# OMODRI_Gate_Driver_1.net
KiCad netlist of a schematic drawn in Altium Designer
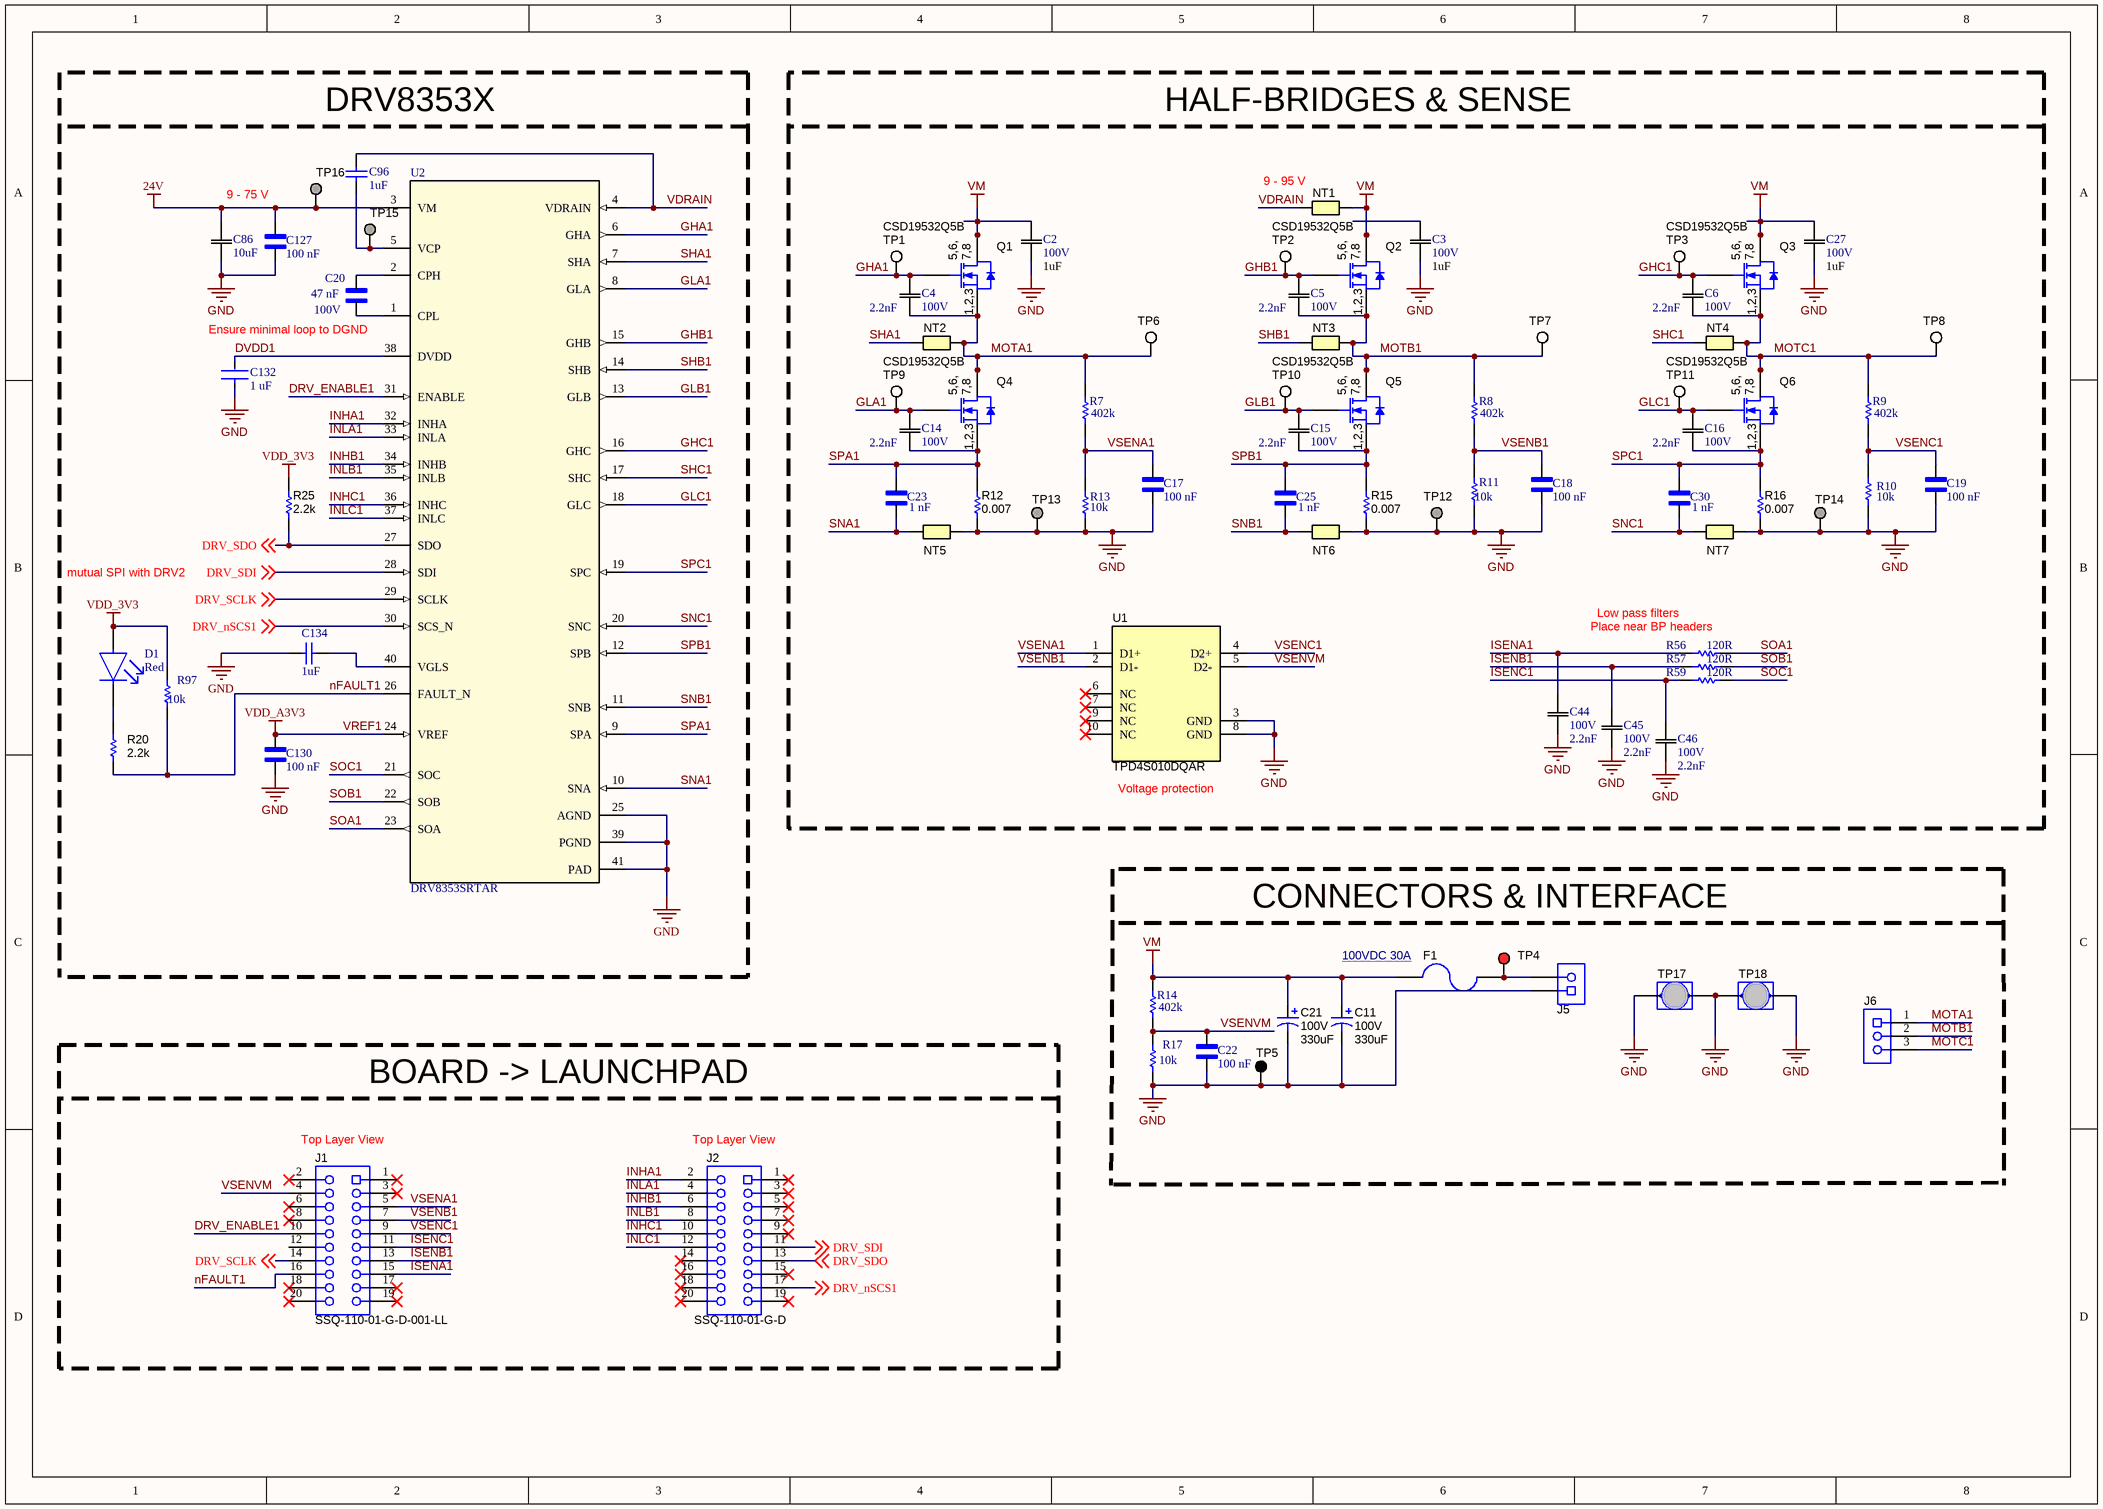
[diagram p0: OMODRI_Gate_Driver_1.SchDoc]

(export (version "E")
  (design (tool "Eeschema 10.0.6"))
  (components
    (comp (ref "C2")
      (value "1uF")
      (footprint "0805_AVX")
      (description "Cap Ceramic 1uF 100V X7R 10% Pad SMD 0805 Soft Termination 125C Automotive T/R")
      (fields
        (field (name "MANUFACTURER_PART_NUMBER") "08051C102K4Z2A")
        (field (name "MANUFACTURER") "Kyocera AVX")
        (field (name "VOLTAGE") "100V")
        (field (name "COPYRIGHT") "Copyright (C) 2018 Accelerated Designs. All rights reserved")
      )
      (libsource (lib "AVX-Capacitor") (part "08051C105K4Z2A"))
    )
    (comp (ref "C3")
      (value "1uF")
      (footprint "0805_AVX")
      (description "Cap Ceramic 1uF 100V X7R 10% Pad SMD 0805 Soft Termination 125C Automotive T/R")
      (fields
        (field (name "MANUFACTURER_PART_NUMBER") "08051C102K4Z2A")
        (field (name "MANUFACTURER") "Kyocera AVX")
        (field (name "VOLTAGE") "100V")
        (field (name "COPYRIGHT") "Copyright (C) 2018 Accelerated Designs. All rights reserved")
      )
      (libsource (lib "AVX-Capacitor") (part "08051C105K4Z2A"))
    )
    (comp (ref "C4")
      (value "Part Number: C1005X8R2A222K050BA")
      (footprint "CAP_1005")
      (description "CAP CER 2200PF 100V X8R 0402")
      (fields
        (field (name "MANUFACTURER_PART_NUMBER") "C1005X8R2A222K050BA")
        (field (name "MANUFACTURER") "TDK")
        (field (name "VOLTAGE RATING (DC)") "100V")
        (field (name "CAPACITANCE") "2.2nF")
        (field (name "COPYRIGHT") "Copyright (C) 2018 Accelerated Designs. All rights reserved")
      )
      (libsource (lib "TDK-Capacitor") (part "C1005X8R2A222K05"))
    )
    (comp (ref "C5")
      (value "Part Number: C1005X8R2A222K050BA")
      (footprint "CAP_1005")
      (description "CAP CER 2200PF 100V X8R 0402")
      (fields
        (field (name "MANUFACTURER_PART_NUMBER") "C1005X8R2A222K050BA")
        (field (name "MANUFACTURER") "TDK")
        (field (name "VOLTAGE RATING (DC)") "100V")
        (field (name "CAPACITANCE") "2.2nF")
        (field (name "COPYRIGHT") "Copyright (C) 2018 Accelerated Designs. All rights reserved")
      )
      (libsource (lib "TDK-Capacitor") (part "C1005X8R2A222K05"))
    )
    (comp (ref "C6")
      (value "Part Number: C1005X8R2A222K050BA")
      (footprint "CAP_1005")
      (description "CAP CER 2200PF 100V X8R 0402")
      (fields
        (field (name "MANUFACTURER_PART_NUMBER") "C1005X8R2A222K050BA")
        (field (name "MANUFACTURER") "TDK")
        (field (name "VOLTAGE RATING (DC)") "100V")
        (field (name "CAPACITANCE") "2.2nF")
        (field (name "COPYRIGHT") "Copyright (C) 2018 Accelerated Designs. All rights reserved")
      )
      (libsource (lib "TDK-Capacitor") (part "C1005X8R2A222K05"))
    )
    (comp (ref "C11")
      (value "EEV-FK2A331M")
      (footprint "SM_RADIAL_K16")
      (description "CAP, AL, 330 uF, 100 V, +/- 20%, 0.153 ohm, AEC-Q200 Grade 2, SMD")
      (fields
        (field (name "MANUFACTURER") "Panasonic")
        (field (name "VDC_V") "100V")
        (field (name "VALUEDISPLAYED") "330uF")
        (field (name "PUBLISHER") "Texas Instruments")
      )
      (libsource (lib "Altium Vault - TI") (part "Cap_Polarized"))
    )
    (comp (ref "C14")
      (value "Part Number: C1005X8R2A222K050BA")
      (footprint "CAP_1005")
      (description "CAP CER 2200PF 100V X8R 0402")
      (fields
        (field (name "MANUFACTURER_PART_NUMBER") "C1005X8R2A222K050BA")
        (field (name "MANUFACTURER") "TDK")
        (field (name "VOLTAGE RATING (DC)") "100V")
        (field (name "CAPACITANCE") "2.2nF")
        (field (name "COPYRIGHT") "Copyright (C) 2018 Accelerated Designs. All rights reserved")
      )
      (libsource (lib "TDK-Capacitor") (part "C1005X8R2A222K05"))
    )
    (comp (ref "C15")
      (value "Part Number: C1005X8R2A222K050BA")
      (footprint "CAP_1005")
      (description "CAP CER 2200PF 100V X8R 0402")
      (fields
        (field (name "MANUFACTURER_PART_NUMBER") "C1005X8R2A222K050BA")
        (field (name "MANUFACTURER") "TDK")
        (field (name "VOLTAGE RATING (DC)") "100V")
        (field (name "CAPACITANCE") "2.2nF")
        (field (name "COPYRIGHT") "Copyright (C) 2018 Accelerated Designs. All rights reserved")
      )
      (libsource (lib "TDK-Capacitor") (part "C1005X8R2A222K05"))
    )
    (comp (ref "C16")
      (value "Part Number: C1005X8R2A222K050BA")
      (footprint "CAP_1005")
      (description "CAP CER 2200PF 100V X8R 0402")
      (fields
        (field (name "MANUFACTURER_PART_NUMBER") "C1005X8R2A222K050BA")
        (field (name "MANUFACTURER") "TDK")
        (field (name "VOLTAGE RATING (DC)") "100V")
        (field (name "CAPACITANCE") "2.2nF")
        (field (name "COPYRIGHT") "Copyright (C) 2018 Accelerated Designs. All rights reserved")
      )
      (libsource (lib "TDK-Capacitor") (part "C1005X8R2A222K05"))
    )
    (comp (ref "C17")
      (value "100 nF")
      (footprint "CAPC0603X33N")
      (description "SMD Capacitor X5R_EIA_ with Capacitance: 0.10uF Tol. 10%. Rated Voltage: 25Vdc")
      (fields (field (name "MF") "Murata") (field (name "MP") "GRM033R61E104KE14D"))
      (libsource (lib "GRM033R61E104KE14D") (part "GRM033R61E104KE14D"))
    )
    (comp (ref "C18")
      (value "100 nF")
      (footprint "CAPC0603X33N")
      (description "SMD Capacitor X5R_EIA_ with Capacitance: 0.10uF Tol. 10%. Rated Voltage: 25Vdc")
      (fields (field (name "MF") "Murata") (field (name "MP") "GRM033R61E104KE14D"))
      (libsource (lib "GRM033R61E104KE14D") (part "GRM033R61E104KE14D"))
    )
    (comp (ref "C19")
      (value "100 nF")
      (footprint "CAPC0603X33N")
      (description "SMD Capacitor X5R_EIA_ with Capacitance: 0.10uF Tol. 10%. Rated Voltage: 25Vdc")
      (fields (field (name "MF") "Murata") (field (name "MP") "GRM033R61E104KE14D"))
      (libsource (lib "GRM033R61E104KE14D") (part "GRM033R61E104KE14D"))
    )
    (comp (ref "C20")
      (value "47 nF")
      (footprint "CAPC1608X90N")
      (description "SMD Capacitor X8R_EIA_ with Capacitance: 47000pF Tol. 10%. Rated Voltage: 100Vdc")
      (fields
        (field (name "DIGI-KEY_PART_NUMBER") "490-GCG188R92A473KA01DCT-ND")
        (field (name "MP") "GCG188R92A473KA01D")
        (field (name "VOLTAGE") "100V")
      )
      (libsource (lib "Murata-Capacitor") (part "GCG188R92A473KA01D"))
    )
    (comp (ref "C21")
      (value "EEV-FK2A331M")
      (footprint "SM_RADIAL_K16")
      (description "CAP, AL, 330 uF, 100 V, +/- 20%, 0.153 ohm, AEC-Q200 Grade 2, SMD")
      (fields
        (field (name "MANUFACTURER") "Panasonic")
        (field (name "VDC_V") "100V")
        (field (name "VALUEDISPLAYED") "330uF")
        (field (name "PUBLISHER") "Texas Instruments")
      )
      (libsource (lib "Altium Vault - TI") (part "CMP-0011224-2"))
    )
    (comp (ref "C22")
      (value "100 nF")
      (footprint "CAPC0603X33N")
      (description "SMD Capacitor X5R_EIA_ with Capacitance: 0.10uF Tol. 10%. Rated Voltage: 25Vdc")
      (fields (field (name "MF") "Murata") (field (name "MP") "GRM033R61E104KE14D"))
      (libsource (lib "GRM033R61E104KE14D") (part "GRM033R61E104KE14D"))
    )
    (comp (ref "C23")
      (value "1 nF")
      (footprint "CAPC0603X33N")
      (description "SMD Capacitor X7R_EIA_ with Capacitance: 1000pF Tol. 10%. Rated Voltage: 50Vdc")
      (fields (field (name "DIGI-KEY_PART_NUMBER") "490-10682-1-ND") (field (name "MP") "GRM033R71H102KA12D"))
      (libsource (lib "Murata-CapacitorGRM") (part "GRM033R71H102KA12D"))
    )
    (comp (ref "C25")
      (value "1 nF")
      (footprint "CAPC0603X33N")
      (description "SMD Capacitor X7R_EIA_ with Capacitance: 1000pF Tol. 10%. Rated Voltage: 50Vdc")
      (fields (field (name "DIGI-KEY_PART_NUMBER") "490-10682-1-ND") (field (name "MP") "GRM033R71H102KA12D"))
      (libsource (lib "Murata-CapacitorGRM") (part "GRM033R71H102KA12D"))
    )
    (comp (ref "C27")
      (value "1uF")
      (footprint "0805_AVX")
      (description "Cap Ceramic 1uF 100V X7R 10% Pad SMD 0805 Soft Termination 125C Automotive T/R")
      (fields
        (field (name "MANUFACTURER_PART_NUMBER") "08051C102K4Z2A")
        (field (name "MANUFACTURER") "Kyocera AVX")
        (field (name "VOLTAGE") "100V")
        (field (name "COPYRIGHT") "Copyright (C) 2018 Accelerated Designs. All rights reserved")
      )
      (libsource (lib "AVX-Capacitor") (part "08051C105K4Z2A"))
    )
    (comp (ref "C30")
      (value "1 nF")
      (footprint "CAPC0603X33N")
      (description "SMD Capacitor X7R_EIA_ with Capacitance: 1000pF Tol. 10%. Rated Voltage: 50Vdc")
      (fields (field (name "DIGI-KEY_PART_NUMBER") "490-10682-1-ND") (field (name "MP") "GRM033R71H102KA12D"))
      (libsource (lib "Murata-CapacitorGRM") (part "GRM033R71H102KA12D"))
    )
    (comp (ref "C44")
      (value "Part Number: C1005X8R2A222K050BA")
      (footprint "CAP_1005")
      (description "CAP CER 2200PF 100V X8R 0402")
      (fields
        (field (name "MANUFACTURER_PART_NUMBER") "C1005X8R2A222K050BA")
        (field (name "MANUFACTURER") "TDK")
        (field (name "VOLTAGE RATING (DC)") "100V")
        (field (name "CAPACITANCE") "2.2nF")
        (field (name "COPYRIGHT") "Copyright (C) 2018 Accelerated Designs. All rights reserved")
      )
      (libsource (lib "TDK-Capacitor") (part "C1005X8R2A222K05"))
    )
    (comp (ref "C45")
      (value "Part Number: C1005X8R2A222K050BA")
      (footprint "CAP_1005")
      (description "CAP CER 2200PF 100V X8R 0402")
      (fields
        (field (name "MANUFACTURER_PART_NUMBER") "C1005X8R2A222K050BA")
        (field (name "MANUFACTURER") "TDK")
        (field (name "VOLTAGE RATING (DC)") "100V")
        (field (name "CAPACITANCE") "2.2nF")
        (field (name "COPYRIGHT") "Copyright (C) 2018 Accelerated Designs. All rights reserved")
      )
      (libsource (lib "TDK-Capacitor") (part "C1005X8R2A222K05"))
    )
    (comp (ref "C46")
      (value "Part Number: C1005X8R2A222K050BA")
      (footprint "CAP_1005")
      (description "CAP CER 2200PF 100V X8R 0402")
      (fields
        (field (name "MANUFACTURER_PART_NUMBER") "C1005X8R2A222K050BA")
        (field (name "MANUFACTURER") "TDK")
        (field (name "VOLTAGE RATING (DC)") "100V")
        (field (name "CAPACITANCE") "2.2nF")
        (field (name "COPYRIGHT") "Copyright (C) 2018 Accelerated Designs. All rights reserved")
      )
      (libsource (lib "TDK-Capacitor") (part "C1005X8R2A222K05"))
    )
    (comp (ref "C86")
      (value "Part Number: CL10A106MA8NRNC")
      (footprint "CAP_CL10")
      (description "CAP CER 10UF 25V X5R 0603")
      (fields
        (field (name "MANUFACTURER_PART_NUMBER") "CL10A106MA8NRNC")
        (field (name "MANUFACTURER") "Samsung")
        (field (name "CAPACITANCE") "10uF")
        (field (name "COPYRIGHT") "Copyright (C) 2018 Accelerated Designs. All rights reserved")
      )
      (libsource (lib "Samsung-Capacitor") (part "CL10A106MA8NRNC"))
    )
    (comp (ref "C96")
      (value "1uF")
      (footprint "CAPC1005X55X25ML05T10")
      (fields (field (name "PART NUMBER") "GRM155R61C105KA12D") (field (name "MANUFACTURER") "Murata"))
      (libsource (lib "Altium Content Vault") (part "CAP"))
    )
    (comp (ref "C127")
      (value "100 nF")
      (footprint "CAPC0603X33N")
      (description "SMD Capacitor X5R_EIA_ with Capacitance: 0.10uF Tol. 10%. Rated Voltage: 25Vdc")
      (fields (field (name "MF") "Murata") (field (name "MP") "GRM033R61E104KE14D"))
      (libsource (lib "GRM033R61E104KE14D") (part "GRM033R61E104KE14D"))
    )
    (comp (ref "C130")
      (value "100 nF")
      (footprint "CAPC0603X33N")
      (description "SMD Capacitor X5R_EIA_ with Capacitance: 0.10uF Tol. 10%. Rated Voltage: 25Vdc")
      (fields (field (name "MF") "Murata") (field (name "MP") "GRM033R61E104KE14D"))
      (libsource (lib "GRM033R61E104KE14D") (part "GRM033R61E104KE14D"))
    )
    (comp (ref "C132")
      (value "1 uF")
      (footprint "FP-CC0201-BA-MFG")
      (description "CAP CER 1UF 6.3V X5R 0201")
      (fields (field (name "TOLERANCE") "0.2") (field (name "MANUFACTURER") "Yageo"))
      (libsource (lib "Altium Content Vault") (part "11868f565c42a9108669ba33697ecf6"))
    )
    (comp (ref "C134")
      (value "1uF")
      (footprint "CAPC1005X55X25ML05T10")
      (fields (field (name "PART NUMBER") "GRM155R61C105KA12D") (field (name "MANUFACTURER") "Murata"))
      (libsource (lib "Altium Content Vault") (part "CAP"))
    )
    (comp (ref "D1")
      (value "SML-P11UTT86R")
      (footprint "FP-SML-P1-MFG")
      (description "LED, PICOLED, Red, SMD, 1 mA, 1.8 V, 621 nm")
      (fields
        (field (name "MANUFACTURER PART NUMBER") "SML-P11VTT86R")
        (field (name "OCTOPART") "https://octopart.com/sml-p11vtt86r-rohm-34112314")
        (field (name "COLOUR") "Red")
      )
      (libsource (lib "LED") (part "SML-P11UTT86R"))
    )
    (comp (ref "F1")
      (value "100VDC 30A")
      (footprint "Fuse_0463")
      (description "Fuse, 30 A, 250 VAC, 100 VDC, SMD")
      (fields (field (name "PARTNUMBER") "0463030.ER") (field (name "MANUFACTURER") "Littelfuse"))
      (libsource (lib "Altium Vault - TI") (part "CMP-0077200-3"))
    )
    (comp (ref "J1")
      (value "SSQ-110-01-G-D-001-LL")
      (footprint "Samtec_SSQ-110-01-x-D-001-LL")
      (description "Receptacle, 2.54mm, 10x2, Gold, TH")
      (fields (field (name "MANUFACTURER") "Samtec"))
      (libsource (lib "Altium Vault - TI") (part "Receptacle_10x2"))
    )
    (comp (ref "J2")
      (value "SSQ-110-01-G-D")
      (footprint "Samtec_SSQ-110-01-x-D")
      (description "Receptacle, 2.54mm, 10x2, Gold, TH")
      (fields (field (name "MANUFACTURER") "Samtec"))
      (libsource (lib "Altium Vault - TI") (part "CMP-0082605-1"))
    )
    (comp (ref "J5")
      (value "1902547")
      (footprint "Phoenix_1902547")
      (description "Terminal Block, 9.52mm, 2x1, R/A, TH")
      (fields (field (name "MANUFACTURER") "Phoenix Contact") (field (name "PUBLISHER") "Texas Instruments"))
      (libsource (lib "Altium Vault - TI") (part "CMP-0055527-1"))
    )
    (comp (ref "J6")
      (value "1904150")
      (footprint "Phoenix_1904150")
      (description "Terminal Block, 9.52mm, 3x1, R/A, TH")
      (fields (field (name "MANUFACTURER") "Phoenix Contact") (field (name "PUBLISHER") "Texas Instruments"))
      (libsource (lib "Altium Vault - TI") (part "Receptacle_3x1"))
    )
    (comp (ref "NT1")
      (value "Net-Tie")
      (footprint "Net-Tie_50milWide_30milLong")
      (description "Single point connection between nets.")
      (libsource (lib "Altium Vault - TI") (part "Net-Tie"))
    )
    (comp (ref "NT2")
      (value "Net-Tie")
      (footprint "Net-Tie_10mil")
      (description "Single point connection between nets.")
      (libsource (lib "Altium Vault - TI") (part "Net-Tie"))
    )
    (comp (ref "NT3")
      (value "Net-Tie")
      (footprint "Net-Tie_10mil")
      (description "Single point connection between nets.")
      (libsource (lib "Altium Vault - TI") (part "Net-Tie"))
    )
    (comp (ref "NT4")
      (value "Net-Tie")
      (footprint "Net-Tie_10mil")
      (description "Single point connection between nets.")
      (libsource (lib "Altium Vault - TI") (part "Net-Tie"))
    )
    (comp (ref "NT5")
      (value "Net-Tie")
      (footprint "Net-Tie_10mil")
      (description "Single point connection between nets.")
      (libsource (lib "Altium Vault - TI") (part "Net-Tie"))
    )
    (comp (ref "NT6")
      (value "Net-Tie")
      (footprint "Net-Tie_10mil")
      (description "Single point connection between nets.")
      (libsource (lib "Altium Vault - TI") (part "Net-Tie"))
    )
    (comp (ref "NT7")
      (value "Net-Tie")
      (footprint "Net-Tie_10mil")
      (description "Single point connection between nets.")
      (libsource (lib "Altium Vault - TI") (part "Net-Tie"))
    )
    (comp (ref "Q1")
      (value "CSD19532Q5B")
      (footprint "DNK0008A")
      (description "MOSFET, N-CH, 100 V, 17 A, DNK0008A (VSON-CLIP-8)")
      (fields (field (name "MANUFACTURER") "Texas Instruments"))
      (libsource (lib "Altium Vault - TI") (part "MOSFET_N_D56789G4S123"))
    )
    (comp (ref "Q2")
      (value "CSD19532Q5B")
      (footprint "DNK0008A")
      (description "MOSFET, N-CH, 100 V, 17 A, DNK0008A (VSON-CLIP-8)")
      (fields (field (name "MANUFACTURER") "Texas Instruments"))
      (libsource (lib "Altium Vault - TI") (part "MOSFET_N_D56789G4S123"))
    )
    (comp (ref "Q3")
      (value "CSD19532Q5B")
      (footprint "DNK0008A")
      (description "MOSFET, N-CH, 100 V, 17 A, DNK0008A (VSON-CLIP-8)")
      (fields (field (name "MANUFACTURER") "Texas Instruments"))
      (libsource (lib "Altium Vault - TI") (part "MOSFET_N_D56789G4S123"))
    )
    (comp (ref "Q4")
      (value "CSD19532Q5B")
      (footprint "DNK0008A")
      (description "MOSFET, N-CH, 100 V, 17 A, DNK0008A (VSON-CLIP-8)")
      (fields (field (name "MANUFACTURER") "Texas Instruments"))
      (libsource (lib "Altium Vault - TI") (part "MOSFET_N_D56789G4S123"))
    )
    (comp (ref "Q5")
      (value "CSD19532Q5B")
      (footprint "DNK0008A")
      (description "MOSFET, N-CH, 100 V, 17 A, DNK0008A (VSON-CLIP-8)")
      (fields (field (name "MANUFACTURER") "Texas Instruments"))
      (libsource (lib "Altium Vault - TI") (part "MOSFET_N_D56789G4S123"))
    )
    (comp (ref "Q6")
      (value "CSD19532Q5B")
      (footprint "DNK0008A")
      (description "MOSFET, N-CH, 100 V, 17 A, DNK0008A (VSON-CLIP-8)")
      (fields (field (name "MANUFACTURER") "Texas Instruments"))
      (libsource (lib "Altium Vault - TI") (part "MOSFET_N_D56789G4S123"))
    )
    (comp (ref "R7")
      (value "ERJ-2RKF4023X")
      (footprint "RESC1005X40X25LL05T05")
      (description "RES SMD 402K OHM 1% 1/10W 0402")
      (fields (field (name "MANUFACTURER") "Panasonic") (field (name "RESISTANCE") "402k"))
      (libsource (lib "Altium Content Vault") (part "RES"))
    )
    (comp (ref "R8")
      (value "ERJ-2RKF4023X")
      (footprint "RESC1005X40X25LL05T05")
      (description "RES SMD 402K OHM 1% 1/10W 0402")
      (fields (field (name "MANUFACTURER") "Panasonic") (field (name "RESISTANCE") "402k"))
      (libsource (lib "Altium Content Vault") (part "RES"))
    )
    (comp (ref "R9")
      (value "ERJ-2RKF4023X")
      (footprint "RESC1005X40X25LL05T05")
      (description "RES SMD 402K OHM 1% 1/10W 0402")
      (fields (field (name "MANUFACTURER") "Panasonic") (field (name "RESISTANCE") "402k"))
      (libsource (lib "Altium Content Vault") (part "RES"))
    )
    (comp (ref "R10")
      (value "ERJ2RKF1002X")
      (footprint "RESC1005X40X25LL05T05")
      (description "Chip Resistor, 10 KOhm, +/- 1%, 0.1 W, -55 to 155 degC, 0402 (1005 Metric), RoHS, Tape and Reel")
      (fields
        (field (name "RESISTANCE") "10k")
        (field (name "TOLERANCE") "1%")
        (field (name "MANUFACTURER") "Panasonic")
      )
      (libsource (lib "Altium Content Vault") (part "RES-2"))
    )
    (comp (ref "R11")
      (value "ERJ2RKF1002X")
      (footprint "RESC1005X40X25LL05T05")
      (description "Chip Resistor, 10 KOhm, +/- 1%, 0.1 W, -55 to 155 degC, 0402 (1005 Metric), RoHS, Tape and Reel")
      (fields
        (field (name "RESISTANCE") "10k")
        (field (name "TOLERANCE") "1%")
        (field (name "MANUFACTURER") "Panasonic")
      )
      (libsource (lib "Altium Content Vault") (part "RES-2"))
    )
    (comp (ref "R12")
      (value "CRE2512-FZ-R007E-3")
      (footprint "CRE2512-R5_R9")
      (description "RES, 0.007, 1%, 3 W, AEC-Q200 Grade 0, 2512")
      (fields
        (field (name "VALUEDISPLAYED") "0.007")
        (field (name "MANUFACTURER") "Bourns")
        (field (name "PUBLISHER") "Texas Instruments")
      )
      (libsource (lib "Altium Vault - TI") (part "Resistor"))
    )
    (comp (ref "R13")
      (value "ERJ2RKF1002X")
      (footprint "RESC1005X40X25LL05T05")
      (description "Chip Resistor, 10 KOhm, +/- 1%, 0.1 W, -55 to 155 degC, 0402 (1005 Metric), RoHS, Tape and Reel")
      (fields
        (field (name "RESISTANCE") "10k")
        (field (name "TOLERANCE") "1%")
        (field (name "MANUFACTURER") "Panasonic")
      )
      (libsource (lib "Altium Content Vault") (part "RES-2"))
    )
    (comp (ref "R14")
      (value "ERJ-2RKF4023X")
      (footprint "RESC1005X40X25LL05T05")
      (description "RES SMD 402K OHM 1% 1/10W 0402")
      (fields (field (name "MANUFACTURER") "Panasonic") (field (name "RESISTANCE") "402k"))
      (libsource (lib "Altium Content Vault") (part "RES"))
    )
    (comp (ref "R15")
      (value "CRE2512-FZ-R007E-3")
      (footprint "CRE2512-R5_R9")
      (description "RES, 0.007, 1%, 3 W, AEC-Q200 Grade 0, 2512")
      (fields
        (field (name "VALUEDISPLAYED") "0.007")
        (field (name "MANUFACTURER") "Bourns")
        (field (name "PUBLISHER") "Texas Instruments")
      )
      (libsource (lib "Altium Vault - TI") (part "Resistor"))
    )
    (comp (ref "R16")
      (value "CRE2512-FZ-R007E-3")
      (footprint "CRE2512-R5_R9")
      (description "RES, 0.007, 1%, 3 W, AEC-Q200 Grade 0, 2512")
      (fields
        (field (name "VALUEDISPLAYED") "0.007")
        (field (name "MANUFACTURER") "Bourns")
        (field (name "PUBLISHER") "Texas Instruments")
      )
      (libsource (lib "Altium Vault - TI") (part "Resistor"))
    )
    (comp (ref "R17")
      (value "ERJ2RKF1002X")
      (footprint "RESC1005X40X25LL05T05")
      (description "Chip Resistor, 10 KOhm, +/- 1%, 0.1 W, -55 to 155 degC, 0402 (1005 Metric), RoHS, Tape and Reel")
      (fields
        (field (name "RESISTANCE") "10k")
        (field (name "TOLERANCE") "1%")
        (field (name "MANUFACTURER") "Panasonic")
      )
      (libsource (lib "Altium Content Vault") (part "RES-2"))
    )
    (comp (ref "R20")
      (value "CRCW04022K20JNED")
      (footprint "0402")
      (description "RES, 2.2 k, 5%, 0.063 W, AEC-Q200 Grade 0, 0402")
      (fields (field (name "MANUFACTURER") "Vishay-Dale") (field (name "VALUEDISPLAYED") "2.2k"))
      (libsource (lib "Altium Vault - TI") (part "Resistor"))
    )
    (comp (ref "R25")
      (value "CRCW04022K20JNED")
      (footprint "0402")
      (description "RES, 2.2 k, 5%, 0.063 W, AEC-Q200 Grade 0, 0402")
      (fields (field (name "MANUFACTURER") "Vishay-Dale") (field (name "VALUEDISPLAYED") "2.2k"))
      (libsource (lib "Altium Vault - TI") (part "Resistor"))
    )
    (comp (ref "R56")
      (value "CRCW0402120RJNEDHP")
      (footprint "RESC1005X40X25ML05T10")
      (description "RES SMD 120 OHM 5% 1/5W 0402")
      (fields
        (field (name "MANUFACTURER") "Vishay Dale")
        (field (name "TOLERANCE") "5%")
        (field (name "RESISTANCE") "120R")
      )
      (libsource (lib "Vishay-Resistor") (part "CRCW0402120RJNEDHP"))
    )
    (comp (ref "R57")
      (value "CRCW0402120RJNEDHP")
      (footprint "RESC1005X40X25ML05T10")
      (description "RES SMD 120 OHM 5% 1/5W 0402")
      (fields
        (field (name "MANUFACTURER") "Vishay Dale")
        (field (name "TOLERANCE") "5%")
        (field (name "RESISTANCE") "120R")
      )
      (libsource (lib "Vishay-Resistor") (part "CRCW0402120RJNEDHP"))
    )
    (comp (ref "R59")
      (value "CRCW0402120RJNEDHP")
      (footprint "RESC1005X40X25ML05T10")
      (description "RES SMD 120 OHM 5% 1/5W 0402")
      (fields
        (field (name "MANUFACTURER") "Vishay Dale")
        (field (name "TOLERANCE") "5%")
        (field (name "RESISTANCE") "120R")
      )
      (libsource (lib "Vishay-Resistor") (part "CRCW0402120RJNEDHP"))
    )
    (comp (ref "R97")
      (value "ERJ2RKF1002X")
      (footprint "RESC1005X40X25LL05T05")
      (description "Chip Resistor, 10 KOhm, +/- 1%, 0.1 W, -55 to 155 degC, 0402 (1005 Metric), RoHS, Tape and Reel")
      (fields
        (field (name "RESISTANCE") "10k")
        (field (name "TOLERANCE") "1%")
        (field (name "MANUFACTURER") "Panasonic")
      )
      (libsource (lib "Altium Content Vault") (part "RES-2"))
    )
    (comp (ref "TP1")
      (value "5002")
      (footprint "Keystone5002")
      (description "Test Point, Miniature, White, TH")
      (fields (field (name "MANUFACTURER") "Keystone") (field (name "PUBLISHER") "Texas Instruments"))
      (libsource (lib "Altium Vault - TI") (part "5002"))
    )
    (comp (ref "TP2")
      (value "5002")
      (footprint "Keystone5002")
      (description "Test Point, Miniature, White, TH")
      (fields (field (name "MANUFACTURER") "Keystone") (field (name "PUBLISHER") "Texas Instruments"))
      (libsource (lib "Altium Vault - TI") (part "5002"))
    )
    (comp (ref "TP3")
      (value "5002")
      (footprint "Keystone5002")
      (description "Test Point, Miniature, White, TH")
      (fields (field (name "MANUFACTURER") "Keystone") (field (name "PUBLISHER") "Texas Instruments"))
      (libsource (lib "Altium Vault - TI") (part "5002"))
    )
    (comp (ref "TP4")
      (value "5000")
      (footprint "Keystone5000")
      (description "Test Point, Miniature, Red, TH")
      (fields (field (name "MANUFACTURER") "Keystone") (field (name "PUBLISHER") "Texas Instruments"))
      (libsource (lib "Altium Vault - TI") (part "5000"))
    )
    (comp (ref "TP5")
      (value "5001")
      (footprint "Keystone5001")
      (description "Test Point, Miniature, Black, TH")
      (fields (field (name "MANUFACTURER") "Keystone") (field (name "PUBLISHER") "Texas Instruments"))
      (libsource (lib "Altium Vault - TI") (part "5001"))
    )
    (comp (ref "TP6")
      (value "5002")
      (footprint "Keystone5002")
      (description "Test Point, Miniature, White, TH")
      (fields (field (name "MANUFACTURER") "Keystone") (field (name "PUBLISHER") "Texas Instruments"))
      (libsource (lib "Altium Vault - TI") (part "5002"))
    )
    (comp (ref "TP7")
      (value "5002")
      (footprint "Keystone5002")
      (description "Test Point, Miniature, White, TH")
      (fields (field (name "MANUFACTURER") "Keystone") (field (name "PUBLISHER") "Texas Instruments"))
      (libsource (lib "Altium Vault - TI") (part "5002"))
    )
    (comp (ref "TP8")
      (value "5002")
      (footprint "Keystone5002")
      (description "Test Point, Miniature, White, TH")
      (fields (field (name "MANUFACTURER") "Keystone") (field (name "PUBLISHER") "Texas Instruments"))
      (libsource (lib "Altium Vault - TI") (part "5002"))
    )
    (comp (ref "TP9")
      (value "5002")
      (footprint "Keystone5002")
      (description "Test Point, Miniature, White, TH")
      (fields (field (name "MANUFACTURER") "Keystone") (field (name "PUBLISHER") "Texas Instruments"))
      (libsource (lib "Altium Vault - TI") (part "5002"))
    )
    (comp (ref "TP10")
      (value "5002")
      (footprint "Keystone5002")
      (description "Test Point, Miniature, White, TH")
      (fields (field (name "MANUFACTURER") "Keystone") (field (name "PUBLISHER") "Texas Instruments"))
      (libsource (lib "Altium Vault - TI") (part "5002"))
    )
    (comp (ref "TP11")
      (value "5002")
      (footprint "Keystone5002")
      (description "Test Point, Miniature, White, TH")
      (fields (field (name "MANUFACTURER") "Keystone") (field (name "PUBLISHER") "Texas Instruments"))
      (libsource (lib "Altium Vault - TI") (part "5002"))
    )
    (comp (ref "TP12")
      (value "TP_SM_1MM")
      (footprint "TP_SM_1MM")
      (description "1mm Test Point, SMT")
      (fields (field (name "MANUFACTURER") "Any") (field (name "PUBLISHER") "Texas Instruments"))
      (libsource (lib "Altium Vault - TI") (part "TESTPOINT"))
    )
    (comp (ref "TP13")
      (value "TP_SM_1MM")
      (footprint "TP_SM_1MM")
      (description "1mm Test Point, SMT")
      (fields (field (name "MANUFACTURER") "Any") (field (name "PUBLISHER") "Texas Instruments"))
      (libsource (lib "Altium Vault - TI") (part "TESTPOINT"))
    )
    (comp (ref "TP14")
      (value "TP_SM_1MM")
      (footprint "TP_SM_1MM")
      (description "1mm Test Point, SMT")
      (fields (field (name "MANUFACTURER") "Any") (field (name "PUBLISHER") "Texas Instruments"))
      (libsource (lib "Altium Vault - TI") (part "TESTPOINT"))
    )
    (comp (ref "TP15")
      (value "TP_SM_1MM")
      (footprint "TP_SM_1MM")
      (description "1mm Test Point, SMT")
      (fields (field (name "MANUFACTURER") "Any") (field (name "PUBLISHER") "Texas Instruments"))
      (libsource (lib "Altium Vault - TI") (part "TESTPOINT"))
    )
    (comp (ref "TP16")
      (value "TP_SM_1MM")
      (footprint "TP_SM_1MM")
      (description "1mm Test Point, SMT")
      (fields (field (name "MANUFACTURER") "Any") (field (name "PUBLISHER") "Texas Instruments"))
      (libsource (lib "Altium Vault - TI") (part "TESTPOINT"))
    )
    (comp (ref "TP17")
      (value "D3082-05")
      (footprint "Harwin_D3082-05")
      (description "1mm Uninsulated Shorting Plug, 10.16mm spacing, TH")
      (fields (field (name "MANUFACTURER") "Harwin") (field (name "PUBLISHER") "Texas Instruments"))
      (libsource (lib "Altium Vault - TI") (part "Jumper_2p"))
    )
    (comp (ref "TP18")
      (value "D3082-05")
      (footprint "Harwin_D3082-05")
      (description "1mm Uninsulated Shorting Plug, 10.16mm spacing, TH")
      (fields (field (name "MANUFACTURER") "Harwin") (field (name "PUBLISHER") "Texas Instruments"))
      (libsource (lib "Altium Vault - TI") (part "Jumper_2p"))
    )
    (comp (ref "U1")
      (value "TPD4S010DQAR")
      (footprint "DQA0010A")
      (fields (field (name "MANUFACTURER") "Texas Instruments") (field (name "PARTNUMBER") "TPD4S010DQAR"))
      (libsource (lib "Altium Vault - TI") (part "TI-TPD4S010-SON_DQA-10"))
    )
    (comp (ref "U2")
      (value "DRV8353SRTAR")
      (footprint "RTA0040B")
      (fields (field (name "MANUFACTURER") "Texas Instruments"))
      (libsource (lib "Texas_Instruments") (part "DRV8353SRTAR"))
    )
  )
  (nets
    (net (code "1") (name "/DRV_ENABLE1") (class "Default")
      (node (ref "J1") (pin "10") (pinfunction "10_10") (pintype "passive"))
      (node (ref "U2") (pin "31") (pinfunction "ENABLE_31") (pintype "input"))
    )
    (net (code "2") (name "/DVDD1") (class "Default")
      (node (ref "C132") (pin "2") (pinfunction "2_2") (pintype "passive"))
      (node (ref "U2") (pin "38") (pinfunction "DVDD_38") (pintype "power_in"))
    )
    (net (code "3") (name "/GHA1") (class "Default")
      (node (ref "C4") (pin "2") (pinfunction "2_2") (pintype "passive"))
      (node (ref "Q1") (pin "4") (pinfunction "G_4") (pintype "passive"))
      (node (ref "TP1") (pin "1") (pintype "passive"))
      (node (ref "U2") (pin "6") (pinfunction "GHA_6") (pintype "output"))
    )
    (net (code "4") (name "/GHB1") (class "Default")
      (node (ref "C5") (pin "2") (pinfunction "2_2") (pintype "passive"))
      (node (ref "Q2") (pin "4") (pinfunction "G_4") (pintype "passive"))
      (node (ref "TP2") (pin "1") (pintype "passive"))
      (node (ref "U2") (pin "15") (pinfunction "GHB_15") (pintype "output"))
    )
    (net (code "5") (name "/GHC1") (class "Default")
      (node (ref "C6") (pin "2") (pinfunction "2_2") (pintype "passive"))
      (node (ref "Q3") (pin "4") (pinfunction "G_4") (pintype "passive"))
      (node (ref "TP3") (pin "1") (pintype "passive"))
      (node (ref "U2") (pin "16") (pinfunction "GHC_16") (pintype "output"))
    )
    (net (code "6") (name "/GLA1") (class "Default")
      (node (ref "C14") (pin "2") (pinfunction "2_2") (pintype "passive"))
      (node (ref "Q4") (pin "4") (pinfunction "G_4") (pintype "passive"))
      (node (ref "TP9") (pin "1") (pintype "passive"))
      (node (ref "U2") (pin "8") (pinfunction "GLA_8") (pintype "output"))
    )
    (net (code "7") (name "/GLB1") (class "Default")
      (node (ref "C15") (pin "2") (pinfunction "2_2") (pintype "passive"))
      (node (ref "Q5") (pin "4") (pinfunction "G_4") (pintype "passive"))
      (node (ref "TP10") (pin "1") (pintype "passive"))
      (node (ref "U2") (pin "13") (pinfunction "GLB_13") (pintype "output"))
    )
    (net (code "8") (name "/GLC1") (class "Default")
      (node (ref "C16") (pin "2") (pinfunction "2_2") (pintype "passive"))
      (node (ref "Q6") (pin "4") (pinfunction "G_4") (pintype "passive"))
      (node (ref "TP11") (pin "1") (pintype "passive"))
      (node (ref "U2") (pin "18") (pinfunction "GLC_18") (pintype "output"))
    )
    (net (code "9") (name "/INHA1") (class "Default")
      (node (ref "J2") (pin "2") (pinfunction "2_2") (pintype "passive"))
      (node (ref "U2") (pin "32") (pinfunction "INHA_32") (pintype "input"))
    )
    (net (code "10") (name "/INHB1") (class "Default")
      (node (ref "J2") (pin "6") (pinfunction "6_6") (pintype "passive"))
      (node (ref "U2") (pin "34") (pinfunction "INHB_34") (pintype "input"))
    )
    (net (code "11") (name "/INHC1") (class "Default")
      (node (ref "J2") (pin "10") (pinfunction "10_10") (pintype "passive"))
      (node (ref "U2") (pin "36") (pinfunction "INHC_36") (pintype "input"))
    )
    (net (code "12") (name "/INLA1") (class "Default")
      (node (ref "J2") (pin "4") (pinfunction "4_4") (pintype "passive"))
      (node (ref "U2") (pin "33") (pinfunction "INLA_33") (pintype "input"))
    )
    (net (code "13") (name "/INLB1") (class "Default")
      (node (ref "J2") (pin "8") (pinfunction "8_8") (pintype "passive"))
      (node (ref "U2") (pin "35") (pinfunction "INLB_35") (pintype "input"))
    )
    (net (code "14") (name "/INLC1") (class "Default")
      (node (ref "J2") (pin "12") (pinfunction "12_12") (pintype "passive"))
      (node (ref "U2") (pin "37") (pinfunction "INLC_37") (pintype "input"))
    )
    (net (code "15") (name "/ISENA1") (class "Default")
      (node (ref "C44") (pin "2") (pinfunction "2_2") (pintype "passive"))
      (node (ref "J1") (pin "15") (pinfunction "15_15") (pintype "passive"))
      (node (ref "R56") (pin "2") (pinfunction "2_2") (pintype "passive"))
    )
    (net (code "16") (name "/ISENB1") (class "Default")
      (node (ref "C45") (pin "2") (pinfunction "2_2") (pintype "passive"))
      (node (ref "J1") (pin "13") (pinfunction "13_13") (pintype "passive"))
      (node (ref "R57") (pin "2") (pinfunction "2_2") (pintype "passive"))
    )
    (net (code "17") (name "/ISENC1") (class "Default")
      (node (ref "C46") (pin "2") (pinfunction "2_2") (pintype "passive"))
      (node (ref "J1") (pin "11") (pinfunction "11_11") (pintype "passive"))
      (node (ref "R59") (pin "2") (pinfunction "2_2") (pintype "passive"))
    )
    (net (code "18") (name "/MOTA1") (class "Default")
      (node (ref "C4") (pin "1") (pinfunction "1_1") (pintype "passive"))
      (node (ref "J6") (pin "1") (pinfunction "1_1") (pintype "passive"))
      (node (ref "NT2") (pin "2") (pinfunction "2_2") (pintype "passive"))
      (node (ref "Q1") (pin "1") (pinfunction "S_1") (pintype "passive"))
      (node (ref "Q1") (pin "2") (pinfunction "S_2") (pintype "passive"))
      (node (ref "Q1") (pin "3") (pinfunction "S_3") (pintype "passive"))
      (node (ref "Q4") (pin "5") (pinfunction "D_5") (pintype "passive"))
      (node (ref "Q4") (pin "6") (pinfunction "D_6") (pintype "passive"))
      (node (ref "Q4") (pin "7") (pinfunction "D_7") (pintype "passive"))
      (node (ref "Q4") (pin "8") (pinfunction "D_8") (pintype "passive"))
      (node (ref "Q4") (pin "9") (pinfunction "D_9") (pintype "passive"))
      (node (ref "R7") (pin "2") (pinfunction "2_2") (pintype "passive"))
      (node (ref "TP6") (pin "1") (pintype "passive"))
    )
    (net (code "19") (name "/MOTB1") (class "Default")
      (node (ref "C5") (pin "1") (pinfunction "1_1") (pintype "passive"))
      (node (ref "J6") (pin "2") (pinfunction "2_2") (pintype "passive"))
      (node (ref "NT3") (pin "2") (pinfunction "2_2") (pintype "passive"))
      (node (ref "Q2") (pin "1") (pinfunction "S_1") (pintype "passive"))
      (node (ref "Q2") (pin "2") (pinfunction "S_2") (pintype "passive"))
      (node (ref "Q2") (pin "3") (pinfunction "S_3") (pintype "passive"))
      (node (ref "Q5") (pin "5") (pinfunction "D_5") (pintype "passive"))
      (node (ref "Q5") (pin "6") (pinfunction "D_6") (pintype "passive"))
      (node (ref "Q5") (pin "7") (pinfunction "D_7") (pintype "passive"))
      (node (ref "Q5") (pin "8") (pinfunction "D_8") (pintype "passive"))
      (node (ref "Q5") (pin "9") (pinfunction "D_9") (pintype "passive"))
      (node (ref "R8") (pin "2") (pinfunction "2_2") (pintype "passive"))
      (node (ref "TP7") (pin "1") (pintype "passive"))
    )
    (net (code "20") (name "/MOTC1") (class "Default")
      (node (ref "C6") (pin "1") (pinfunction "1_1") (pintype "passive"))
      (node (ref "J6") (pin "3") (pinfunction "3_3") (pintype "passive"))
      (node (ref "NT4") (pin "2") (pinfunction "2_2") (pintype "passive"))
      (node (ref "Q3") (pin "1") (pinfunction "S_1") (pintype "passive"))
      (node (ref "Q3") (pin "2") (pinfunction "S_2") (pintype "passive"))
      (node (ref "Q3") (pin "3") (pinfunction "S_3") (pintype "passive"))
      (node (ref "Q6") (pin "5") (pinfunction "D_5") (pintype "passive"))
      (node (ref "Q6") (pin "6") (pinfunction "D_6") (pintype "passive"))
      (node (ref "Q6") (pin "7") (pinfunction "D_7") (pintype "passive"))
      (node (ref "Q6") (pin "8") (pinfunction "D_8") (pintype "passive"))
      (node (ref "Q6") (pin "9") (pinfunction "D_9") (pintype "passive"))
      (node (ref "R9") (pin "2") (pinfunction "2_2") (pintype "passive"))
      (node (ref "TP8") (pin "1") (pintype "passive"))
    )
    (net (code "21") (name "/SHA1") (class "Default")
      (node (ref "NT2") (pin "1") (pinfunction "1_1") (pintype "passive"))
      (node (ref "U2") (pin "7") (pinfunction "SHA_7") (pintype "input"))
    )
    (net (code "22") (name "/SHB1") (class "Default")
      (node (ref "NT3") (pin "1") (pinfunction "1_1") (pintype "passive"))
      (node (ref "U2") (pin "14") (pinfunction "SHB_14") (pintype "input"))
    )
    (net (code "23") (name "/SHC1") (class "Default")
      (node (ref "NT4") (pin "1") (pinfunction "1_1") (pintype "passive"))
      (node (ref "U2") (pin "17") (pinfunction "SHC_17") (pintype "input"))
    )
    (net (code "24") (name "/SNA1") (class "Default")
      (node (ref "C23") (pin "1") (pinfunction "1_1") (pintype "passive"))
      (node (ref "NT5") (pin "1") (pinfunction "1_1") (pintype "passive"))
      (node (ref "U2") (pin "10") (pinfunction "SNA_10") (pintype "input"))
    )
    (net (code "25") (name "/SNB1") (class "Default")
      (node (ref "C25") (pin "1") (pinfunction "1_1") (pintype "passive"))
      (node (ref "NT6") (pin "1") (pinfunction "1_1") (pintype "passive"))
      (node (ref "U2") (pin "11") (pinfunction "SNB_11") (pintype "input"))
    )
    (net (code "26") (name "/SNC1") (class "Default")
      (node (ref "C30") (pin "1") (pinfunction "1_1") (pintype "passive"))
      (node (ref "NT7") (pin "1") (pinfunction "1_1") (pintype "passive"))
      (node (ref "U2") (pin "20") (pinfunction "SNC_20") (pintype "input"))
    )
    (net (code "27") (name "/SOA1") (class "Default")
      (node (ref "R56") (pin "1") (pinfunction "1_1") (pintype "passive"))
      (node (ref "U2") (pin "23") (pinfunction "SOA_23") (pintype "output"))
    )
    (net (code "28") (name "/SOB1") (class "Default")
      (node (ref "R57") (pin "1") (pinfunction "1_1") (pintype "passive"))
      (node (ref "U2") (pin "22") (pinfunction "SOB_22") (pintype "output"))
    )
    (net (code "29") (name "/SOC1") (class "Default")
      (node (ref "R59") (pin "1") (pinfunction "1_1") (pintype "passive"))
      (node (ref "U2") (pin "21") (pinfunction "SOC_21") (pintype "output"))
    )
    (net (code "30") (name "/SPA1") (class "Default")
      (node (ref "C14") (pin "1") (pinfunction "1_1") (pintype "passive"))
      (node (ref "C23") (pin "2") (pinfunction "2_2") (pintype "passive"))
      (node (ref "Q4") (pin "1") (pinfunction "S_1") (pintype "passive"))
      (node (ref "Q4") (pin "2") (pinfunction "S_2") (pintype "passive"))
      (node (ref "Q4") (pin "3") (pinfunction "S_3") (pintype "passive"))
      (node (ref "R12") (pin "2") (pinfunction "2_2") (pintype "passive"))
      (node (ref "U2") (pin "9") (pinfunction "SPA_9") (pintype "input"))
    )
    (net (code "31") (name "/SPB1") (class "Default")
      (node (ref "C15") (pin "1") (pinfunction "1_1") (pintype "passive"))
      (node (ref "C25") (pin "2") (pinfunction "2_2") (pintype "passive"))
      (node (ref "Q5") (pin "1") (pinfunction "S_1") (pintype "passive"))
      (node (ref "Q5") (pin "2") (pinfunction "S_2") (pintype "passive"))
      (node (ref "Q5") (pin "3") (pinfunction "S_3") (pintype "passive"))
      (node (ref "R15") (pin "2") (pinfunction "2_2") (pintype "passive"))
      (node (ref "U2") (pin "12") (pinfunction "SPB_12") (pintype "input"))
    )
    (net (code "32") (name "/SPC1") (class "Default")
      (node (ref "C16") (pin "1") (pinfunction "1_1") (pintype "passive"))
      (node (ref "C30") (pin "2") (pinfunction "2_2") (pintype "passive"))
      (node (ref "Q6") (pin "1") (pinfunction "S_1") (pintype "passive"))
      (node (ref "Q6") (pin "2") (pinfunction "S_2") (pintype "passive"))
      (node (ref "Q6") (pin "3") (pinfunction "S_3") (pintype "passive"))
      (node (ref "R16") (pin "2") (pinfunction "2_2") (pintype "passive"))
      (node (ref "U2") (pin "19") (pinfunction "SPC_19") (pintype "input"))
    )
    (net (code "33") (name "/VDRAIN") (class "Default")
      (node (ref "C96") (pin "1") (pinfunction "1_1") (pintype "passive"))
      (node (ref "NT1") (pin "1") (pinfunction "1_1") (pintype "passive"))
      (node (ref "U2") (pin "4") (pinfunction "VDRAIN_4") (pintype "input"))
    )
    (net (code "34") (name "/VSENA1") (class "Default")
      (node (ref "C17") (pin "2") (pinfunction "2_2") (pintype "passive"))
      (node (ref "J1") (pin "5") (pinfunction "5_5") (pintype "passive"))
      (node (ref "R13") (pin "2") (pinfunction "2_2") (pintype "passive"))
      (node (ref "R7") (pin "1") (pinfunction "1_1") (pintype "passive"))
      (node (ref "U1") (pin "1") (pinfunction "D1+_1") (pintype "passive"))
    )
    (net (code "35") (name "/VSENB1") (class "Default")
      (node (ref "C18") (pin "2") (pinfunction "2_2") (pintype "passive"))
      (node (ref "J1") (pin "7") (pinfunction "7_7") (pintype "passive"))
      (node (ref "R11") (pin "2") (pinfunction "2_2") (pintype "passive"))
      (node (ref "R8") (pin "1") (pinfunction "1_1") (pintype "passive"))
      (node (ref "U1") (pin "2") (pinfunction "D1-_2") (pintype "passive"))
    )
    (net (code "36") (name "/VSENC1") (class "Default")
      (node (ref "C19") (pin "2") (pinfunction "2_2") (pintype "passive"))
      (node (ref "J1") (pin "9") (pinfunction "9_9") (pintype "passive"))
      (node (ref "R10") (pin "2") (pinfunction "2_2") (pintype "passive"))
      (node (ref "R9") (pin "1") (pinfunction "1_1") (pintype "passive"))
      (node (ref "U1") (pin "4") (pinfunction "D2+_4") (pintype "passive"))
    )
    (net (code "37") (name "/VSENVM") (class "Default")
      (node (ref "C22") (pin "2") (pinfunction "2_2") (pintype "passive"))
      (node (ref "J1") (pin "4") (pinfunction "4_4") (pintype "passive"))
      (node (ref "R14") (pin "1") (pinfunction "1_1") (pintype "passive"))
      (node (ref "R17") (pin "2") (pinfunction "2_2") (pintype "passive"))
      (node (ref "U1") (pin "5") (pinfunction "D2-_5") (pintype "passive"))
    )
    (net (code "38") (name "/nFAULT1") (class "Default")
      (node (ref "J1") (pin "16") (pinfunction "16_16") (pintype "passive"))
      (node (ref "R20") (pin "1") (pinfunction "1_1") (pintype "passive"))
      (node (ref "R97") (pin "1") (pinfunction "1_1") (pintype "passive"))
      (node (ref "U2") (pin "26") (pinfunction "FAULT_N_26") (pintype "open_collector"))
    )
    (net (code "39") (name "24V") (class "Default")
      (node (ref "C127") (pin "2") (pinfunction "2_2") (pintype "passive"))
      (node (ref "C86") (pin "2") (pinfunction "2_2") (pintype "passive"))
      (node (ref "TP16") (pin "1") (pintype "passive"))
      (node (ref "U2") (pin "3") (pinfunction "VM_3") (pintype "power_in"))
    )
    (net (code "40") (name "DRV_SCLK") (class "Default")
      (node (ref "J1") (pin "14") (pinfunction "14_14") (pintype "passive"))
      (node (ref "U2") (pin "29") (pinfunction "SCLK_29") (pintype "input"))
    )
    (net (code "41") (name "DRV_SDI") (class "Default")
      (node (ref "J2") (pin "11") (pinfunction "11_11") (pintype "passive"))
      (node (ref "U2") (pin "28") (pinfunction "SDI_28") (pintype "input"))
    )
    (net (code "42") (name "DRV_SDO") (class "Default")
      (node (ref "J2") (pin "13") (pinfunction "13_13") (pintype "passive"))
      (node (ref "R25") (pin "2") (pinfunction "2_2") (pintype "passive"))
      (node (ref "U2") (pin "27") (pinfunction "SDO_27") (pintype "passive"))
    )
    (net (code "43") (name "DRV_nSCS1") (class "Default")
      (node (ref "J2") (pin "17") (pinfunction "17_17") (pintype "passive"))
      (node (ref "U2") (pin "30") (pinfunction "SCS_N_30") (pintype "input"))
    )
    (net (code "44") (name "GND") (class "Default")
      (node (ref "C11") (pin "2") (pinfunction "-_2") (pintype "passive"))
      (node (ref "C127") (pin "1") (pinfunction "1_1") (pintype "passive"))
      (node (ref "C130") (pin "1") (pinfunction "1_1") (pintype "passive"))
      (node (ref "C132") (pin "1") (pinfunction "1_1") (pintype "passive"))
      (node (ref "C134") (pin "2") (pinfunction "2_2") (pintype "passive"))
      (node (ref "C17") (pin "1") (pinfunction "1_1") (pintype "passive"))
      (node (ref "C18") (pin "1") (pinfunction "1_1") (pintype "passive"))
      (node (ref "C19") (pin "1") (pinfunction "1_1") (pintype "passive"))
      (node (ref "C2") (pin "1") (pinfunction "1_1") (pintype "passive"))
      (node (ref "C21") (pin "2") (pinfunction "-_2") (pintype "passive"))
      (node (ref "C22") (pin "1") (pinfunction "1_1") (pintype "passive"))
      (node (ref "C27") (pin "1") (pinfunction "1_1") (pintype "passive"))
      (node (ref "C3") (pin "1") (pinfunction "1_1") (pintype "passive"))
      (node (ref "C44") (pin "1") (pinfunction "1_1") (pintype "passive"))
      (node (ref "C45") (pin "1") (pinfunction "1_1") (pintype "passive"))
      (node (ref "C46") (pin "1") (pinfunction "1_1") (pintype "passive"))
      (node (ref "C86") (pin "1") (pinfunction "1_1") (pintype "passive"))
      (node (ref "J5") (pin "1") (pinfunction "1_1") (pintype "passive"))
      (node (ref "NT5") (pin "2") (pinfunction "2_2") (pintype "passive"))
      (node (ref "NT6") (pin "2") (pinfunction "2_2") (pintype "passive"))
      (node (ref "NT7") (pin "2") (pinfunction "2_2") (pintype "passive"))
      (node (ref "R10") (pin "1") (pinfunction "1_1") (pintype "passive"))
      (node (ref "R11") (pin "1") (pinfunction "1_1") (pintype "passive"))
      (node (ref "R12") (pin "1") (pinfunction "1_1") (pintype "passive"))
      (node (ref "R13") (pin "1") (pinfunction "1_1") (pintype "passive"))
      (node (ref "R15") (pin "1") (pinfunction "1_1") (pintype "passive"))
      (node (ref "R16") (pin "1") (pinfunction "1_1") (pintype "passive"))
      (node (ref "R17") (pin "1") (pinfunction "1_1") (pintype "passive"))
      (node (ref "TP12") (pin "1") (pintype "passive"))
      (node (ref "TP13") (pin "1") (pintype "passive"))
      (node (ref "TP14") (pin "1") (pintype "passive"))
      (node (ref "TP17") (pin "1") (pinfunction "1_1") (pintype "passive"))
      (node (ref "TP17") (pin "2") (pinfunction "2_2") (pintype "passive"))
      (node (ref "TP18") (pin "1") (pinfunction "1_1") (pintype "passive"))
      (node (ref "TP18") (pin "2") (pinfunction "2_2") (pintype "passive"))
      (node (ref "TP5") (pin "1") (pintype "passive"))
      (node (ref "U1") (pin "3") (pinfunction "GND_3") (pintype "power_in"))
      (node (ref "U1") (pin "8") (pinfunction "GND_8") (pintype "power_in"))
      (node (ref "U2") (pin "25") (pinfunction "AGND_25") (pintype "power_in"))
      (node (ref "U2") (pin "39") (pinfunction "PGND_39") (pintype "power_in"))
      (node (ref "U2") (pin "41") (pinfunction "PAD_41") (pintype "power_in"))
    )
    (net (code "45") (name "Net-(D1-C)") (class "Default")
      (node (ref "D1") (pin "1") (pinfunction "C_1") (pintype "passive"))
      (node (ref "R20") (pin "2") (pinfunction "2_2") (pintype "passive"))
    )
    (net (code "46") (name "Net-(F1-Pad1)") (class "Default")
      (node (ref "F1") (pin "1") (pinfunction "1_1") (pintype "passive"))
      (node (ref "J5") (pin "2") (pinfunction "2_2") (pintype "passive"))
      (node (ref "TP4") (pin "1") (pintype "passive"))
    )
    (net (code "47") (name "Net-(U2-CPH)") (class "Default")
      (node (ref "C20") (pin "2") (pinfunction "2_2") (pintype "passive"))
      (node (ref "U2") (pin "2") (pinfunction "CPH_2") (pintype "passive"))
    )
    (net (code "48") (name "Net-(U2-CPL)") (class "Default")
      (node (ref "C20") (pin "1") (pinfunction "1_1") (pintype "passive"))
      (node (ref "U2") (pin "1") (pinfunction "CPL_1") (pintype "passive"))
    )
    (net (code "49") (name "Net-(U2-VCP)") (class "Default")
      (node (ref "C96") (pin "2") (pinfunction "2_2") (pintype "passive"))
      (node (ref "TP15") (pin "1") (pintype "passive"))
      (node (ref "U2") (pin "5") (pinfunction "VCP_5") (pintype "power_in"))
    )
    (net (code "50") (name "Net-(U2-VGLS)") (class "Default")
      (node (ref "C134") (pin "1") (pinfunction "1_1") (pintype "passive"))
      (node (ref "U2") (pin "40") (pinfunction "VGLS_40") (pintype "power_in"))
    )
    (net (code "51") (name "VDD_3V3") (class "Default")
      (node (ref "D1") (pin "2") (pinfunction "A_2") (pintype "passive"))
      (node (ref "R25") (pin "1") (pinfunction "1_1") (pintype "passive"))
      (node (ref "R97") (pin "2") (pinfunction "2_2") (pintype "passive"))
    )
    (net (code "52") (name "VDD_A3V3") (class "Default")
      (node (ref "C130") (pin "2") (pinfunction "2_2") (pintype "passive"))
      (node (ref "U2") (pin "24") (pinfunction "VREF_24") (pintype "input"))
    )
    (net (code "53") (name "VM") (class "Default")
      (node (ref "C11") (pin "1") (pinfunction "+_1") (pintype "passive"))
      (node (ref "C2") (pin "2") (pinfunction "2_2") (pintype "passive"))
      (node (ref "C21") (pin "1") (pinfunction "+_1") (pintype "passive"))
      (node (ref "C27") (pin "2") (pinfunction "2_2") (pintype "passive"))
      (node (ref "F1") (pin "2") (pinfunction "2_2") (pintype "passive"))
      (node (ref "NT1") (pin "2") (pinfunction "2_2") (pintype "passive"))
      (node (ref "Q1") (pin "5") (pinfunction "D_5") (pintype "passive"))
      (node (ref "Q1") (pin "6") (pinfunction "D_6") (pintype "passive"))
      (node (ref "Q1") (pin "7") (pinfunction "D_7") (pintype "passive"))
      (node (ref "Q1") (pin "8") (pinfunction "D_8") (pintype "passive"))
      (node (ref "Q1") (pin "9") (pinfunction "D_9") (pintype "passive"))
      (node (ref "Q2") (pin "5") (pinfunction "D_5") (pintype "passive"))
      (node (ref "Q2") (pin "6") (pinfunction "D_6") (pintype "passive"))
      (node (ref "Q2") (pin "7") (pinfunction "D_7") (pintype "passive"))
      (node (ref "Q2") (pin "8") (pinfunction "D_8") (pintype "passive"))
      (node (ref "Q2") (pin "9") (pinfunction "D_9") (pintype "passive"))
      (node (ref "Q3") (pin "5") (pinfunction "D_5") (pintype "passive"))
      (node (ref "Q3") (pin "6") (pinfunction "D_6") (pintype "passive"))
      (node (ref "Q3") (pin "7") (pinfunction "D_7") (pintype "passive"))
      (node (ref "Q3") (pin "8") (pinfunction "D_8") (pintype "passive"))
      (node (ref "Q3") (pin "9") (pinfunction "D_9") (pintype "passive"))
      (node (ref "R14") (pin "2") (pinfunction "2_2") (pintype "passive"))
    )
    (net (code "54") (name "unconnected-(C3-Pad2)") (class "Default")
      (node (ref "C3") (pin "2") (pinfunction "2_2") (pintype "passive"))
    )
    (net (code "55") (name "unconnected-(J1-Pad1)") (class "Default")
      (node (ref "J1") (pin "1") (pinfunction "1_1") (pintype "passive+no_connect"))
    )
    (net (code "56") (name "unconnected-(J1-Pad2)") (class "Default")
      (node (ref "J1") (pin "2") (pinfunction "2_2") (pintype "passive+no_connect"))
    )
    (net (code "57") (name "unconnected-(J1-Pad3)") (class "Default")
      (node (ref "J1") (pin "3") (pinfunction "3_3") (pintype "passive+no_connect"))
    )
    (net (code "58") (name "unconnected-(J1-Pad6)") (class "Default")
      (node (ref "J1") (pin "6") (pinfunction "6_6") (pintype "passive+no_connect"))
    )
    (net (code "59") (name "unconnected-(J1-Pad8)") (class "Default")
      (node (ref "J1") (pin "8") (pinfunction "8_8") (pintype "passive+no_connect"))
    )
    (net (code "60") (name "unconnected-(J1-Pad12)") (class "Default")
      (node (ref "J1") (pin "12") (pinfunction "12_12") (pintype "passive"))
    )
    (net (code "61") (name "unconnected-(J1-Pad17)") (class "Default")
      (node (ref "J1") (pin "17") (pinfunction "17_17") (pintype "passive+no_connect"))
    )
    (net (code "62") (name "unconnected-(J1-Pad18)") (class "Default")
      (node (ref "J1") (pin "18") (pinfunction "18_18") (pintype "passive+no_connect"))
    )
    (net (code "63") (name "unconnected-(J1-Pad19)") (class "Default")
      (node (ref "J1") (pin "19") (pinfunction "19_19") (pintype "passive+no_connect"))
    )
    (net (code "64") (name "unconnected-(J1-Pad20)") (class "Default")
      (node (ref "J1") (pin "20") (pinfunction "20_20") (pintype "passive+no_connect"))
    )
    (net (code "65") (name "unconnected-(J2-Pad1)") (class "Default")
      (node (ref "J2") (pin "1") (pinfunction "1_1") (pintype "passive+no_connect"))
    )
    (net (code "66") (name "unconnected-(J2-Pad3)") (class "Default")
      (node (ref "J2") (pin "3") (pinfunction "3_3") (pintype "passive+no_connect"))
    )
    (net (code "67") (name "unconnected-(J2-Pad5)") (class "Default")
      (node (ref "J2") (pin "5") (pinfunction "5_5") (pintype "passive+no_connect"))
    )
    (net (code "68") (name "unconnected-(J2-Pad7)") (class "Default")
      (node (ref "J2") (pin "7") (pinfunction "7_7") (pintype "passive+no_connect"))
    )
    (net (code "69") (name "unconnected-(J2-Pad9)") (class "Default")
      (node (ref "J2") (pin "9") (pinfunction "9_9") (pintype "passive+no_connect"))
    )
    (net (code "70") (name "unconnected-(J2-Pad14)") (class "Default")
      (node (ref "J2") (pin "14") (pinfunction "14_14") (pintype "passive+no_connect"))
    )
    (net (code "71") (name "unconnected-(J2-Pad15)") (class "Default")
      (node (ref "J2") (pin "15") (pinfunction "15_15") (pintype "passive+no_connect"))
    )
    (net (code "72") (name "unconnected-(J2-Pad16)") (class "Default")
      (node (ref "J2") (pin "16") (pinfunction "16_16") (pintype "passive+no_connect"))
    )
    (net (code "73") (name "unconnected-(J2-Pad18)") (class "Default")
      (node (ref "J2") (pin "18") (pinfunction "18_18") (pintype "passive+no_connect"))
    )
    (net (code "74") (name "unconnected-(J2-Pad19)") (class "Default")
      (node (ref "J2") (pin "19") (pinfunction "19_19") (pintype "passive+no_connect"))
    )
    (net (code "75") (name "unconnected-(J2-Pad20)") (class "Default")
      (node (ref "J2") (pin "20") (pinfunction "20_20") (pintype "passive+no_connect"))
    )
    (net (code "76") (name "unconnected-(U1-NC-Pad6)") (class "Default")
      (node (ref "U1") (pin "6") (pinfunction "NC_6") (pintype "passive+no_connect"))
    )
    (net (code "77") (name "unconnected-(U1-NC-Pad7)") (class "Default")
      (node (ref "U1") (pin "7") (pinfunction "NC_7") (pintype "passive+no_connect"))
    )
    (net (code "78") (name "unconnected-(U1-NC-Pad9)") (class "Default")
      (node (ref "U1") (pin "9") (pinfunction "NC_9") (pintype "passive+no_connect"))
    )
    (net (code "79") (name "unconnected-(U1-NC-Pad10)") (class "Default")
      (node (ref "U1") (pin "10") (pinfunction "NC_10") (pintype "passive+no_connect"))
    )
  )
)
